# Circuit_diagram_with_easy_eda.net
KiCad netlist of a schematic drawn in EasyEDA
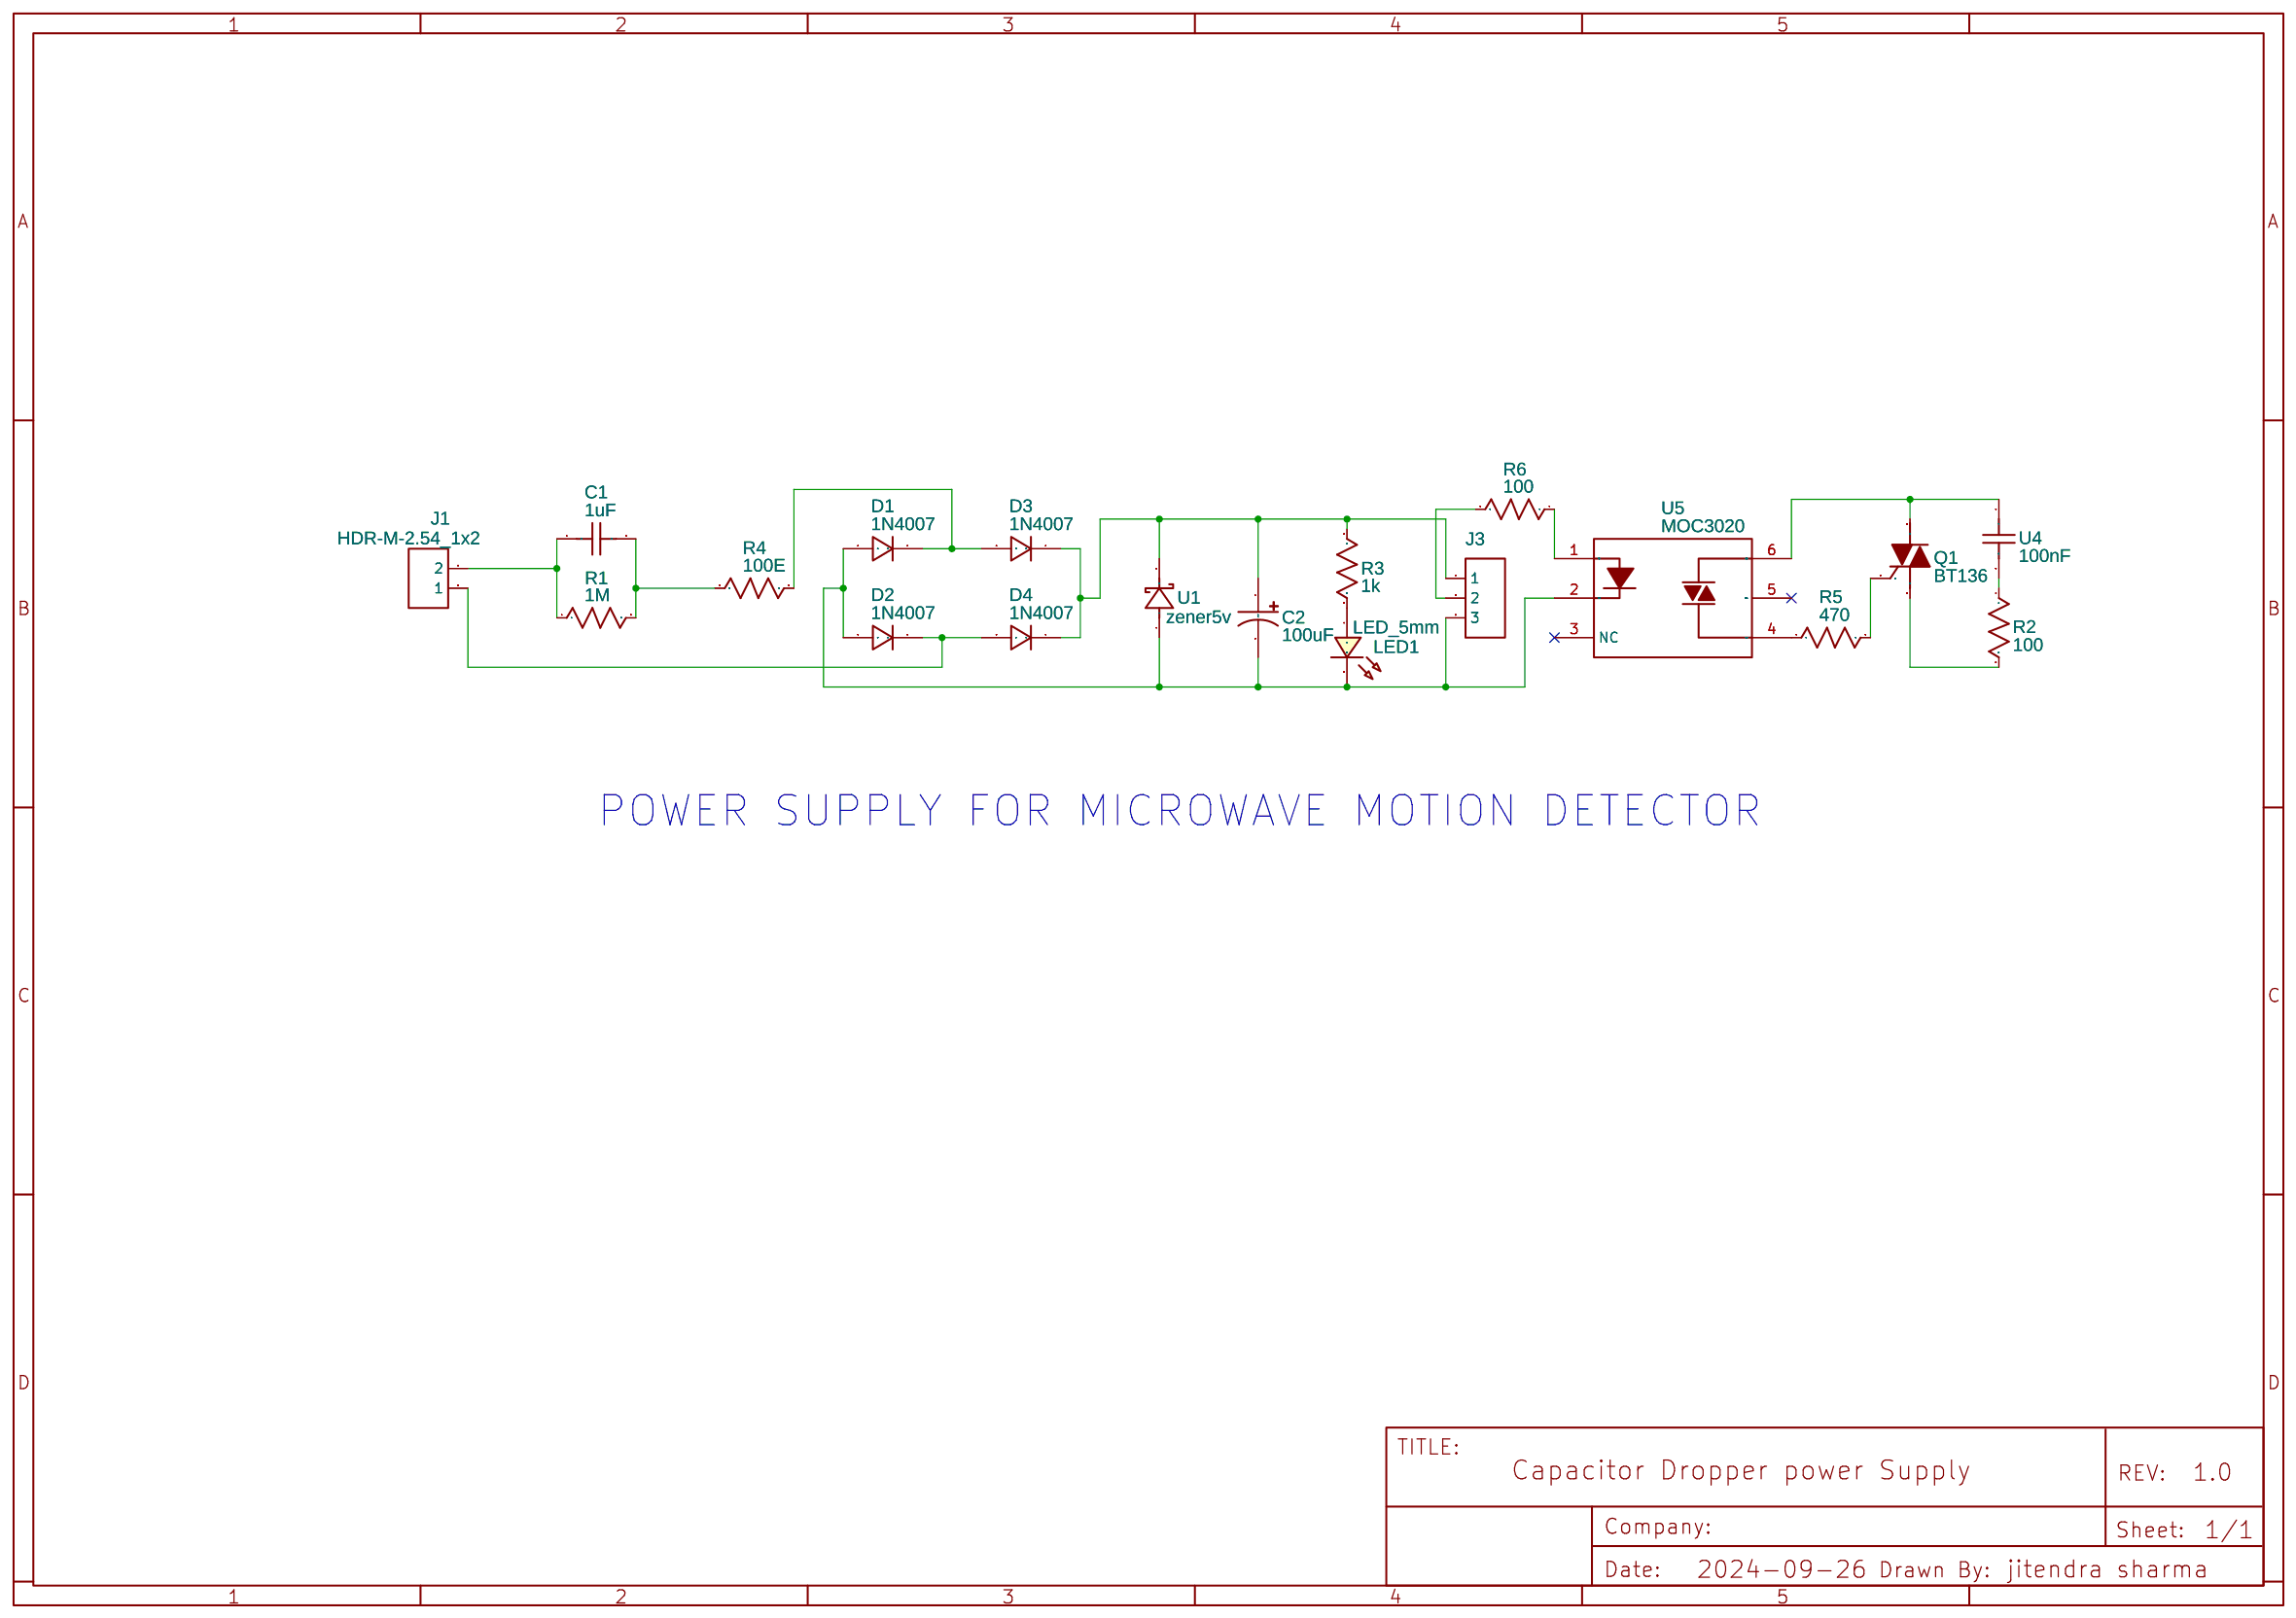
[diagram p0: schematic sheet]

(export (version "E")
  (design (tool "Eeschema 10.0.6"))
  (components
    (comp (ref "C1")
      (value "1uF")
      (fields (field (name "Manufacturer Part") "BFC237321105") (field (name "Manufacturer") "VISHAY(威世)"))
      (libsource (lib "") (part "BFC237321105"))
    )
    (comp (ref "C2")
      (value "100uF")
      (fields
        (field (name "Manufacturer Part") "KNE2100UF25V149EC0011")
        (field (name "Manufacturer") "KNSCHA(科尼盛)")
      )
      (libsource (lib "") (part "KNE2100UF25V149EC0011"))
    )
    (comp (ref "D1")
      (value "1N4007")
      (fields (field (name "Manufacturer") "SEMTECH"))
      (libsource (lib "") (part "1N4007"))
    )
    (comp (ref "D2")
      (value "1N4007")
      (fields (field (name "Manufacturer") "SEMTECH"))
      (libsource (lib "") (part "1N4007"))
    )
    (comp (ref "D3")
      (value "1N4007")
      (fields (field (name "Manufacturer") "SEMTECH"))
      (libsource (lib "") (part "1N4007"))
    )
    (comp (ref "D4")
      (value "1N4007")
      (fields (field (name "Manufacturer") "SEMTECH"))
      (libsource (lib "") (part "1N4007"))
    )
    (comp (ref "J1") (value "HDR-M-2.54_1x2") (libsource (lib "") (part "HDR-M-2.54_1x2")))
    (comp (ref "J3") (value "HDR-M-2.54_1x3") (libsource (lib "") (part "HDR-M-2.54_1x3")))
    (comp (ref "LED1")
      (value "LED_5mm")
      (fields
        (field (name "Manufacturer Part") "333-2SURD/S530-A3")
        (field (name "Manufacturer") "EVERLIGHT(台湾亿光)")
      )
      (libsource (lib "") (part "LED-TH-5mm_R"))
    )
    (comp (ref "Q1")
      (value "BT136")
      (fields (field (name "Manufacturer") "CJ(江苏长电/长晶)"))
      (libsource (lib "") (part "BT136"))
    )
    (comp (ref "R1") (value "1M") (libsource (lib "") (part "R_AXIAL-0.4_US_1")))
    (comp (ref "R2") (value "100") (libsource (lib "") (part "R_AXIAL-0.3_US_1")))
    (comp (ref "R3") (value "1k") (libsource (lib "") (part "R_AXIAL-0.4_US")))
    (comp (ref "R4") (value "100E") (libsource (lib "") (part "R_AXIAL-0.5_US")))
    (comp (ref "R5") (value "470") (libsource (lib "") (part "R_AXIAL-0.3_US")))
    (comp (ref "R6") (value "100") (libsource (lib "") (part "R_AXIAL-0.3_US_2")))
    (comp (ref "U1")
      (value "zener5v")
      (fields (field (name "Manufacturer Part") "1N4007-DIODE"))
      (libsource (lib "") (part "1N4007-DIODE"))
    )
    (comp (ref "U4")
      (value "100nF")
      (fields
        (field (name "Manufacturer Part") "MEB104J100V82CB0018")
        (field (name "Manufacturer") "KNSCHA(科尼盛)")
      )
      (libsource (lib "") (part "MEB104J100V82CB0018"))
    )
    (comp (ref "U5")
      (value "MOC3020")
      (fields (field (name "Manufacturer") "LITEON(光宝)"))
      (libsource (lib "") (part "MOC3020"))
    )
  )
  (nets
    (net (code "1") (name "Net-(C1-Pad1)") (class "Default")
      (node (ref "C1") (pin "1") (pinfunction "1_1") (pintype "unspecified"))
      (node (ref "J1") (pin "2") (pinfunction "2_2") (pintype "unspecified"))
      (node (ref "R1") (pin "1") (pinfunction "1_1") (pintype "unspecified"))
    )
    (net (code "2") (name "Net-(C1-Pad2)") (class "Default")
      (node (ref "C1") (pin "2") (pinfunction "2_2") (pintype "unspecified"))
      (node (ref "R1") (pin "2") (pinfunction "2_2") (pintype "unspecified"))
      (node (ref "R4") (pin "1") (pinfunction "1_1") (pintype "unspecified"))
    )
    (net (code "3") (name "Net-(D1-Pad1)") (class "Default")
      (node (ref "D1") (pin "1") (pinfunction "1_1") (pintype "unspecified"))
      (node (ref "D3") (pin "2") (pinfunction "2_2") (pintype "unspecified"))
      (node (ref "R4") (pin "2") (pinfunction "2_2") (pintype "unspecified"))
    )
    (net (code "4") (name "Net-(D2-Pad1)") (class "Default")
      (node (ref "D2") (pin "1") (pinfunction "1_1") (pintype "unspecified"))
      (node (ref "D4") (pin "2") (pinfunction "2_2") (pintype "unspecified"))
      (node (ref "J1") (pin "1") (pinfunction "1_1") (pintype "unspecified"))
    )
    (net (code "5") (name "Net-(J3-Pad2)") (class "Default")
      (node (ref "J3") (pin "2") (pinfunction "2_2") (pintype "input"))
      (node (ref "R6") (pin "2") (pinfunction "2_2") (pintype "unspecified"))
    )
    (net (code "6") (name "Net-(LED1-Pad1)") (class "Default")
      (node (ref "LED1") (pin "1") (pinfunction "1_1") (pintype "unspecified"))
      (node (ref "R3") (pin "2") (pinfunction "2_2") (pintype "unspecified"))
    )
    (net (code "7") (name "Net-(Q1-G)") (class "Default")
      (node (ref "Q1") (pin "3") (pinfunction "G_3") (pintype "unspecified"))
      (node (ref "R5") (pin "2") (pinfunction "2_2") (pintype "unspecified"))
    )
    (net (code "8") (name "Net-(Q1-M1)") (class "Default")
      (node (ref "Q1") (pin "1") (pinfunction "M1_1") (pintype "unspecified"))
      (node (ref "R2") (pin "2") (pinfunction "2_2") (pintype "unspecified"))
    )
    (net (code "9") (name "Net-(Q1-M2)") (class "Default")
      (node (ref "Q1") (pin "2") (pinfunction "M2_2") (pintype "unspecified"))
      (node (ref "U4") (pin "1") (pinfunction "1_1") (pintype "unspecified"))
      (node (ref "U5") (pin "6") (pinfunction "Terminal__6") (pintype "unspecified"))
    )
    (net (code "10") (name "Net-(R2-Pad1)") (class "Default")
      (node (ref "R2") (pin "1") (pinfunction "1_1") (pintype "unspecified"))
      (node (ref "U4") (pin "2") (pinfunction "2_2") (pintype "unspecified"))
    )
    (net (code "11") (name "Net-(U1-A)") (class "Default")
      (node (ref "C2") (pin "2") (pinfunction "2_2") (pintype "unspecified"))
      (node (ref "D1") (pin "2") (pinfunction "2_2") (pintype "unspecified"))
      (node (ref "D2") (pin "2") (pinfunction "2_2") (pintype "unspecified"))
      (node (ref "J3") (pin "3") (pinfunction "3_3") (pintype "input"))
      (node (ref "LED1") (pin "2") (pinfunction "2_2") (pintype "unspecified"))
      (node (ref "U1") (pin "1") (pinfunction "A_1") (pintype "unspecified"))
      (node (ref "U5") (pin "2") (pinfunction "Cathode__2") (pintype "unspecified"))
    )
    (net (code "12") (name "Net-(U1-K)") (class "Default")
      (node (ref "C2") (pin "1") (pinfunction "1_1") (pintype "unspecified"))
      (node (ref "D3") (pin "1") (pinfunction "1_1") (pintype "unspecified"))
      (node (ref "D4") (pin "1") (pinfunction "1_1") (pintype "unspecified"))
      (node (ref "J3") (pin "1") (pinfunction "1_1") (pintype "input"))
      (node (ref "R3") (pin "1") (pinfunction "1_1") (pintype "unspecified"))
      (node (ref "U1") (pin "2") (pinfunction "K_2") (pintype "unspecified"))
    )
    (net (code "13") (name "Net-(U5-ANODE)") (class "Default")
      (node (ref "R6") (pin "1") (pinfunction "1_1") (pintype "unspecified"))
      (node (ref "U5") (pin "1") (pinfunction "ANODE_1") (pintype "unspecified"))
    )
    (net (code "14") (name "Net-(U5-_Terminal)") (class "Default")
      (node (ref "R5") (pin "1") (pinfunction "1_1") (pintype "unspecified"))
      (node (ref "U5") (pin "4") (pinfunction "_Terminal_4") (pintype "unspecified"))
    )
    (net (code "15") (name "unconnected-(U5-NC-Pad3)") (class "Default")
      (node (ref "U5") (pin "3") (pinfunction "NC_3") (pintype "unspecified+no_connect"))
    )
    (net (code "16") (name "unconnected-(U5-Substrate_-Pad5)") (class "Default")
      (node (ref "U5") (pin "5") (pinfunction "Substrate__5") (pintype "unspecified+no_connect"))
    )
  )
)
